# SCH_10edm_2026-03-11.net
KiCad netlist of a schematic drawn in EasyEDA
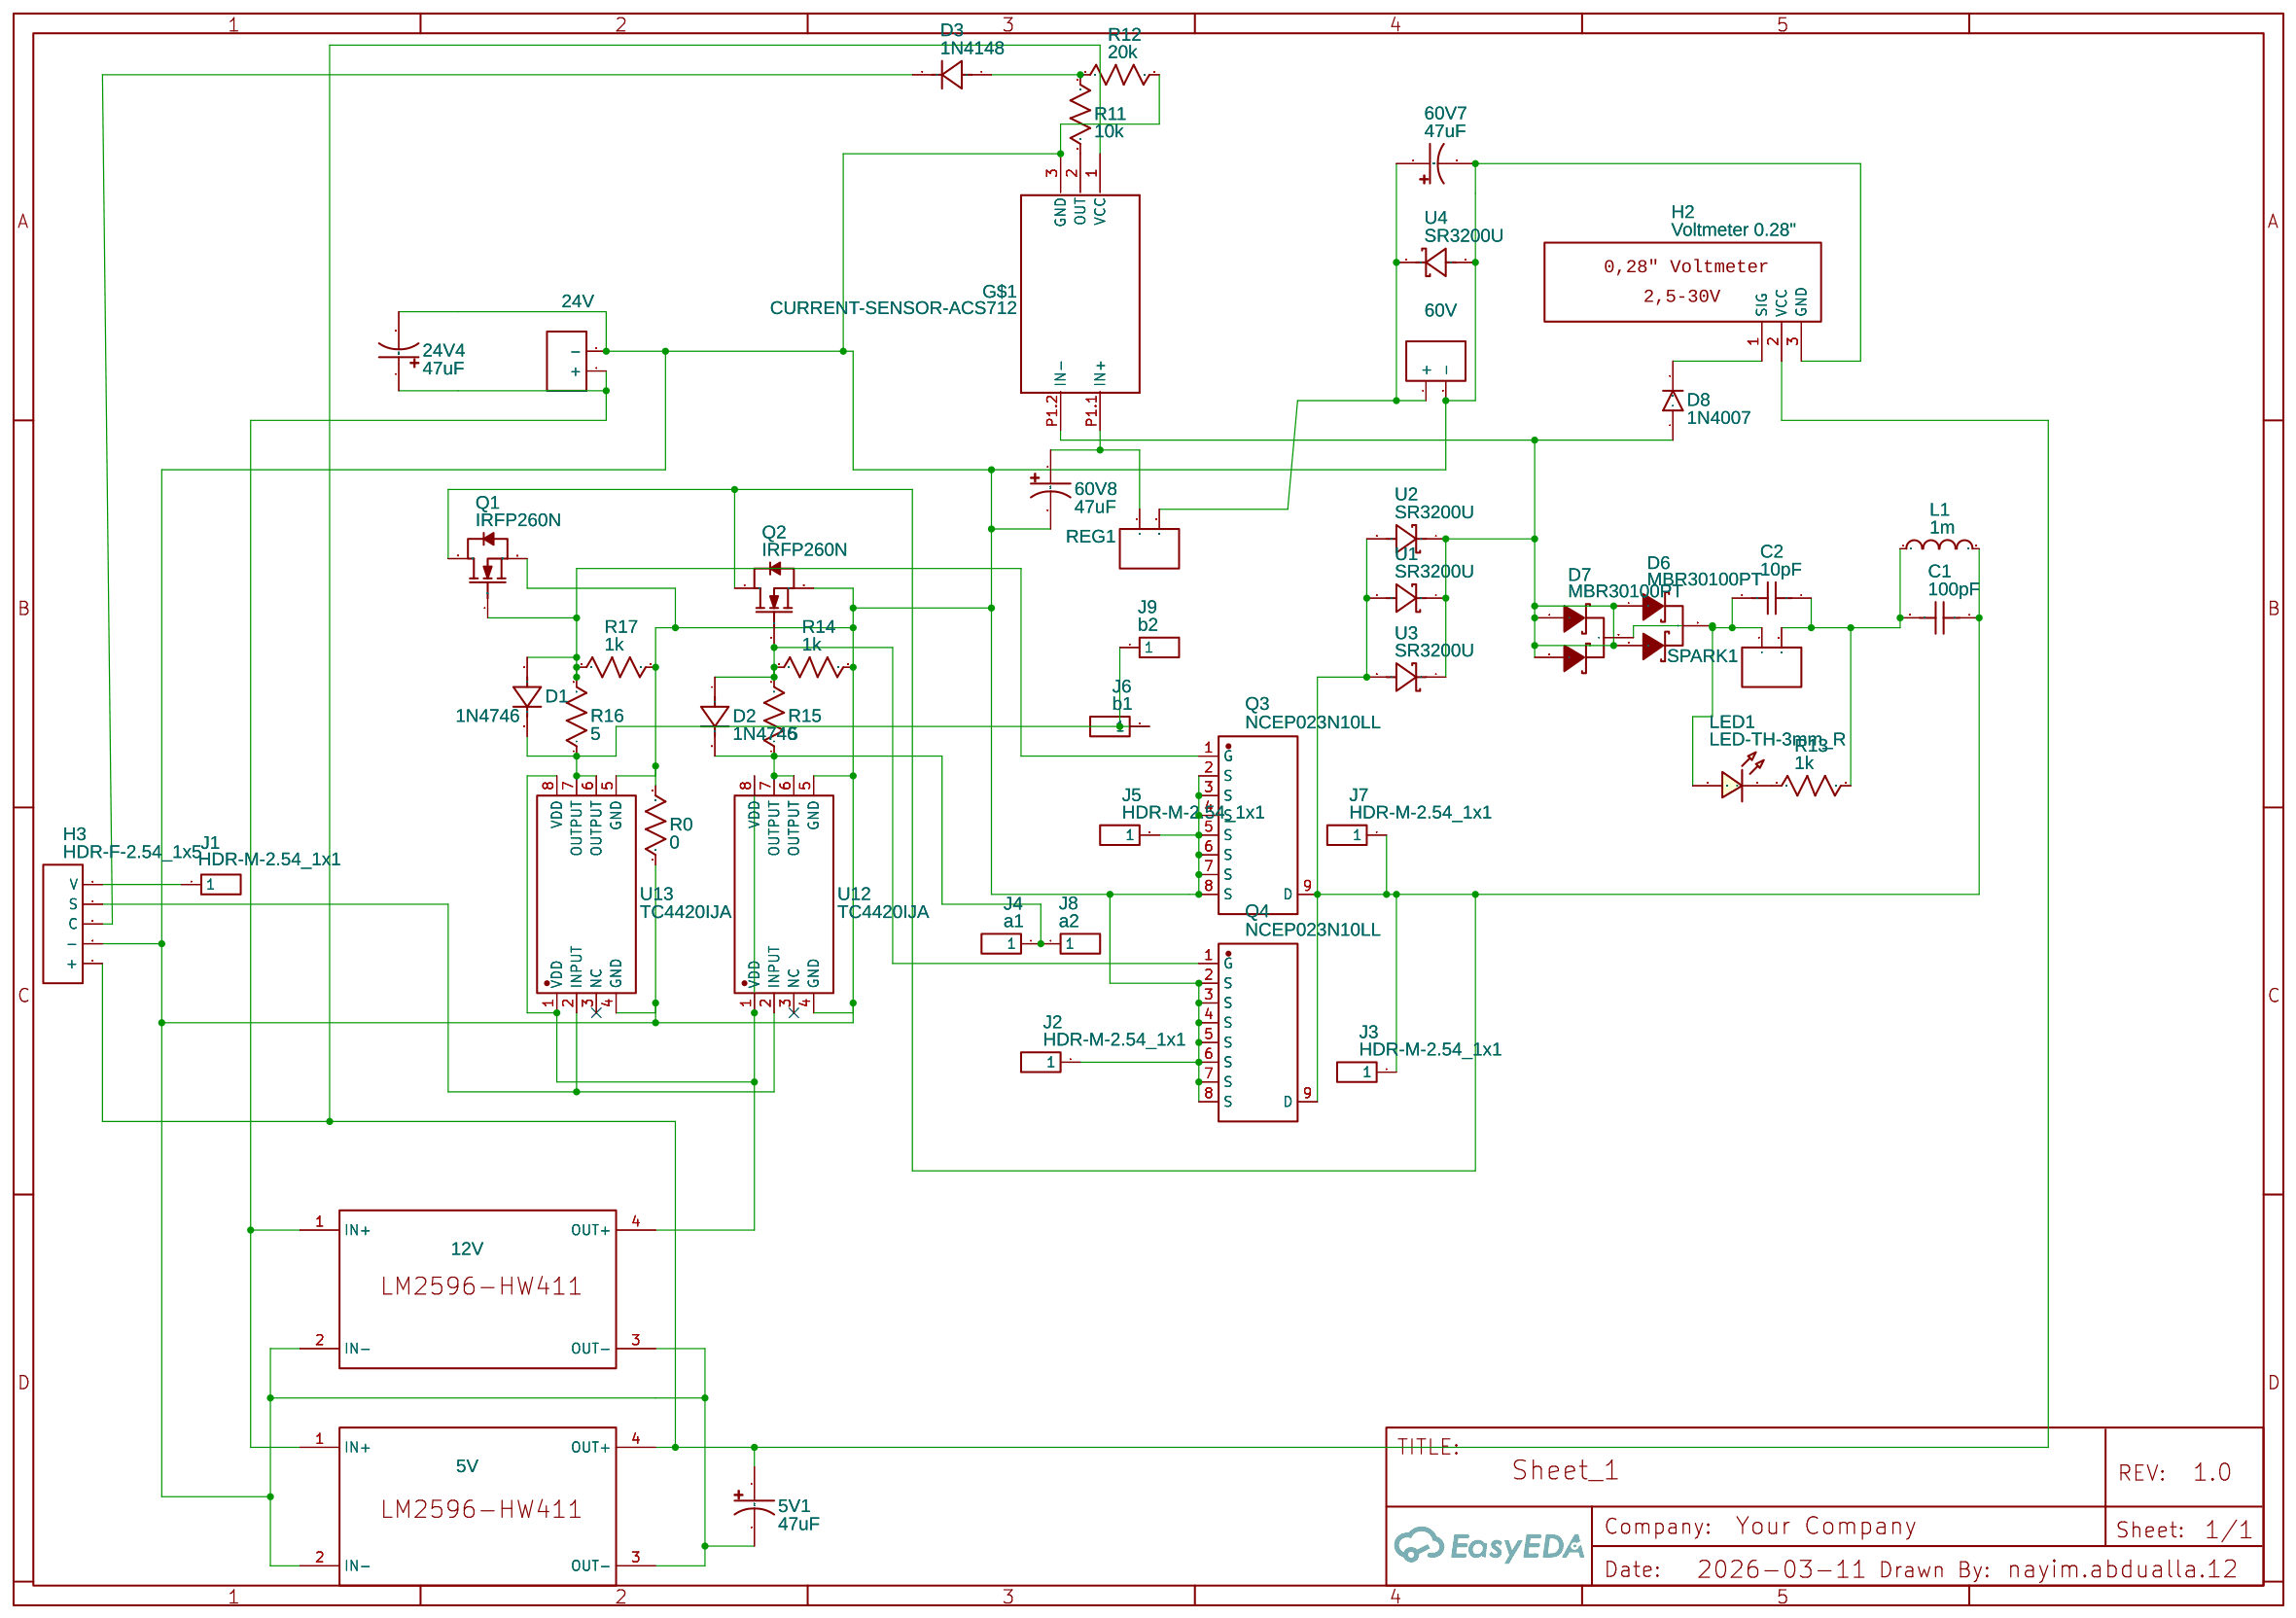
[diagram p0: schematic sheet]

(export (version "E")
  (design (tool "Eeschema 10.0.6"))
  (components
    (comp (ref "5V") (value "LM2596-HW411") (libsource (lib "") (part "LM2596-HW411")))
    (comp (ref "5V1")
      (value "47uF")
      (fields
        (field (name "Manufacturer Part") "NFK160V47M10*16 3.5CC")
        (field (name "Manufacturer") "SAMYOUNG(韩国三莹)")
      )
      (libsource (lib "") (part "NFK160VB47M10*16_3.5CC_3"))
    )
    (comp (ref "12V") (value "LM2596-HW411") (libsource (lib "") (part "LM2596-HW411_1")))
    (comp (ref "24V") (value "CONN-TH_2P-P5.00") (libsource (lib "") (part "CONN-TH_2P-P5.00_2")))
    (comp (ref "24V4")
      (value "47uF")
      (fields
        (field (name "Manufacturer Part") "NFK160V47M10*16 3.5CC")
        (field (name "Manufacturer") "SAMYOUNG(韩国三莹)")
      )
      (libsource (lib "") (part "NFK160VB47M10*16_3.5CC_1"))
    )
    (comp (ref "60V") (value "CONN-TH_2P-P5.00") (libsource (lib "") (part "CONN-TH_2P-P5.00_3")))
    (comp (ref "60V7")
      (value "47uF")
      (fields
        (field (name "Manufacturer Part") "NFK160V47M10*16 3.5CC")
        (field (name "Manufacturer") "SAMYOUNG(韩国三莹)")
      )
      (libsource (lib "") (part "NFK160VB47M10*16_3.5CC"))
    )
    (comp (ref "60V8")
      (value "47uF")
      (fields
        (field (name "Manufacturer Part") "NFK160V47M10*16 3.5CC")
        (field (name "Manufacturer") "SAMYOUNG(韩国三莹)")
      )
      (libsource (lib "") (part "NFK160VB47M10*16_3.5CC_2"))
    )
    (comp (ref "C1")
      (value "100pF")
      (fields (field (name "Manufacturer Part") "R06B1B101KQ0T0S0N0") (field (name "Manufacturer") "STE(松田)"))
      (libsource (lib "") (part "R06B1B101KQ0T0S0N0"))
    )
    (comp (ref "C2")
      (value "10pF")
      (fields (field (name "Manufacturer Part") "R06B1B101KQ0T0S0N0") (field (name "Manufacturer") "STE(松田)"))
      (libsource (lib "") (part "R06B1B101KQ0T0S0N0"))
    )
    (comp (ref "D1")
      (value "1N4746")
      (fields (field (name "Manufacturer Part") "1N4148") (field (name "Manufacturer") "LJ(朗捷)"))
      (libsource (lib "") (part "1N4148_C18195411"))
    )
    (comp (ref "D2")
      (value "1N4746")
      (fields (field (name "Manufacturer Part") "1N4148") (field (name "Manufacturer") "LJ(朗捷)"))
      (libsource (lib "") (part "1N4148_C18195411"))
    )
    (comp (ref "D3")
      (value "1N4148")
      (fields (field (name "Manufacturer") "LJ(朗捷)"))
      (libsource (lib "") (part "1N4148_C18195411_1"))
    )
    (comp (ref "D6")
      (value "MBR30100PT")
      (fields (field (name "Manufacturer") "PANJIT"))
      (libsource (lib "") (part "MBR30100PT"))
    )
    (comp (ref "D7")
      (value "MBR30100PT")
      (fields (field (name "Manufacturer") "PANJIT"))
      (libsource (lib "") (part "MBR30100PT"))
    )
    (comp (ref "D8")
      (value "1N4007")
      (fields (field (name "Manufacturer") "STARSEA"))
      (libsource (lib "") (part "1N4007"))
    )
    (comp (ref "G$1") (value "CURRENT-SENSOR-ACS712") (libsource (lib "") (part "CURRENT-SENSOR-ACS712")))
    (comp (ref "H2") (value "Voltmeter 0.28\"") (libsource (lib "") (part "Voltmeter 0.28{dblquote}")))
    (comp (ref "H3") (value "HDR-F-2.54_1x5") (libsource (lib "") (part "HDR-F-2.54_1x5")))
    (comp (ref "J1") (value "HDR-M-2.54_1x1") (libsource (lib "") (part "HDR-M-2.54_1x1_1")))
    (comp (ref "J2") (value "HDR-M-2.54_1x1") (libsource (lib "") (part "HDR-M-2.54_1x1")))
    (comp (ref "J3") (value "HDR-M-2.54_1x1") (libsource (lib "") (part "HDR-M-2.54_1x1")))
    (comp (ref "J4") (value "a1") (libsource (lib "") (part "HDR-M-2.54_1x1")))
    (comp (ref "J5") (value "HDR-M-2.54_1x1") (libsource (lib "") (part "HDR-M-2.54_1x1")))
    (comp (ref "J6") (value "b1") (libsource (lib "") (part "HDR-M-2.54_1x1")))
    (comp (ref "J7") (value "HDR-M-2.54_1x1") (libsource (lib "") (part "HDR-M-2.54_1x1")))
    (comp (ref "J8") (value "a2") (libsource (lib "") (part "HDR-M-2.54_1x1_1")))
    (comp (ref "J9") (value "b2") (libsource (lib "") (part "HDR-M-2.54_1x1_1")))
    (comp (ref "L1") (value "1m") (libsource (lib "") (part "L_AXIAL-0.6_US")))
    (comp (ref "LED1")
      (value "LED-TH-3mm_R")
      (fields
        (field (name "Manufacturer Part") "204-10SDRD/S530-A3-L")
        (field (name "Manufacturer") "EVERLIGHT(台湾亿光)")
      )
      (libsource (lib "") (part "LED-TH-3mm_R"))
    )
    (comp (ref "Q1")
      (value "IRFP260N")
      (fields (field (name "Manufacturer") "minos(迈诺斯)"))
      (libsource (lib "") (part "IRFP260N"))
    )
    (comp (ref "Q2")
      (value "IRFP260N")
      (fields (field (name "Manufacturer") "minos(迈诺斯)"))
      (libsource (lib "") (part "IRFP260N"))
    )
    (comp (ref "Q3")
      (value "NCEP023N10LL")
      (fields (field (name "Manufacturer") "NCE(无锡新洁能)"))
      (libsource (lib "") (part "NCEP023N10LL"))
    )
    (comp (ref "Q4")
      (value "NCEP023N10LL")
      (fields (field (name "Manufacturer") "NCE(无锡新洁能)"))
      (libsource (lib "") (part "NCEP023N10LL"))
    )
    (comp (ref "R0") (value "0") (libsource (lib "") (part "R_AXIAL-0.4_US_1")))
    (comp (ref "R11") (value "10k") (libsource (lib "") (part "R_AXIAL-0.4_US_1")))
    (comp (ref "R12") (value "20k") (libsource (lib "") (part "R_AXIAL-0.4_US")))
    (comp (ref "R13") (value "1k") (libsource (lib "") (part "R_AXIAL-0.4_US_2")))
    (comp (ref "R14") (value "1k") (libsource (lib "") (part "R_AXIAL-0.4_US")))
    (comp (ref "R15") (value "5") (libsource (lib "") (part "R_AXIAL-0.4_US_1")))
    (comp (ref "R16") (value "5") (libsource (lib "") (part "R_AXIAL-0.4_US_1")))
    (comp (ref "R17") (value "1k") (libsource (lib "") (part "R_AXIAL-0.4_US")))
    (comp (ref "REG1") (value "CONN-TH_2P-P5.00") (libsource (lib "") (part "CONN-TH_2P-P5.00_1")))
    (comp (ref "SPARK1") (value "CONN-TH_2P-P5.00") (libsource (lib "") (part "CONN-TH_2P-P5.00")))
    (comp (ref "U1")
      (value "SR3200U")
      (fields (field (name "Manufacturer") "DIYI(迪一/芯诺)"))
      (libsource (lib "") (part "SR3200U"))
    )
    (comp (ref "U2")
      (value "SR3200U")
      (fields (field (name "Manufacturer") "DIYI(迪一/芯诺)"))
      (libsource (lib "") (part "SR3200U"))
    )
    (comp (ref "U3")
      (value "SR3200U")
      (fields (field (name "Manufacturer") "DIYI(迪一/芯诺)"))
      (libsource (lib "") (part "SR3200U"))
    )
    (comp (ref "U4")
      (value "SR3200U")
      (fields (field (name "Manufacturer") "DIYI(迪一/芯诺)"))
      (libsource (lib "") (part "SR3200U_1"))
    )
    (comp (ref "U12")
      (value "TC4420IJA")
      (fields (field (name "Manufacturer") "MICROCHIP(美国微芯)"))
      (libsource (lib "") (part "TC4420IJA"))
    )
    (comp (ref "U13")
      (value "TC4420IJA")
      (fields (field (name "Manufacturer") "MICROCHIP(美国微芯)"))
      (libsource (lib "") (part "TC4420IJA"))
    )
  )
  (nets
    (net (code "1") (name "Net-(5V-OUT+)") (class "Default")
      (node (ref "5V") (pin "4") (pinfunction "OUT+_4") (pintype "unspecified"))
      (node (ref "5V1") (pin "1") (pinfunction "1_1") (pintype "unspecified"))
      (node (ref "G$1") (pin "1") (pinfunction "VCC_1") (pintype "bidirectional"))
      (node (ref "H2") (pin "2") (pinfunction "VCC_2") (pintype "unspecified"))
      (node (ref "H3") (pin "1") (pinfunction "+_1") (pintype "unspecified"))
    )
    (net (code "2") (name "Net-(12V-IN+)") (class "Default")
      (node (ref "12V") (pin "1") (pinfunction "IN+_1") (pintype "unspecified"))
      (node (ref "24V") (pin "1") (pinfunction "+_1") (pintype "unspecified"))
      (node (ref "24V4") (pin "1") (pinfunction "1_1") (pintype "unspecified"))
      (node (ref "5V") (pin "1") (pinfunction "IN+_1") (pintype "unspecified"))
    )
    (net (code "3") (name "Net-(12V-IN-)") (class "Default")
      (node (ref "12V") (pin "2") (pinfunction "IN-_2") (pintype "unspecified"))
      (node (ref "12V") (pin "3") (pinfunction "OUT-_3") (pintype "unspecified"))
      (node (ref "24V") (pin "2") (pinfunction "-_2") (pintype "unspecified"))
      (node (ref "24V4") (pin "2") (pinfunction "2_2") (pintype "unspecified"))
      (node (ref "5V") (pin "2") (pinfunction "IN-_2") (pintype "unspecified"))
      (node (ref "5V") (pin "3") (pinfunction "OUT-_3") (pintype "unspecified"))
      (node (ref "5V1") (pin "2") (pinfunction "2_2") (pintype "unspecified"))
      (node (ref "60V") (pin "2") (pinfunction "-_2") (pintype "unspecified"))
      (node (ref "60V7") (pin "2") (pinfunction "2_2") (pintype "unspecified"))
      (node (ref "60V8") (pin "2") (pinfunction "2_2") (pintype "unspecified"))
      (node (ref "G$1") (pin "3") (pinfunction "GND_3") (pintype "bidirectional"))
      (node (ref "H2") (pin "3") (pinfunction "GND_3") (pintype "unspecified"))
      (node (ref "H3") (pin "2") (pinfunction "-_2") (pintype "unspecified"))
      (node (ref "J2") (pin "1") (pinfunction "1_1") (pintype "input"))
      (node (ref "J5") (pin "1") (pinfunction "1_1") (pintype "input"))
      (node (ref "Q1") (pin "3") (pinfunction "S_3") (pintype "unspecified"))
      (node (ref "Q2") (pin "3") (pinfunction "S_3") (pintype "unspecified"))
      (node (ref "Q3") (pin "2") (pinfunction "S_2") (pintype "unspecified"))
      (node (ref "Q3") (pin "3") (pinfunction "S_3") (pintype "unspecified"))
      (node (ref "Q3") (pin "4") (pinfunction "S_4") (pintype "unspecified"))
      (node (ref "Q3") (pin "5") (pinfunction "S_5") (pintype "unspecified"))
      (node (ref "Q3") (pin "6") (pinfunction "S_6") (pintype "unspecified"))
      (node (ref "Q3") (pin "7") (pinfunction "S_7") (pintype "unspecified"))
      (node (ref "Q3") (pin "8") (pinfunction "S_8") (pintype "unspecified"))
      (node (ref "Q4") (pin "2") (pinfunction "S_2") (pintype "unspecified"))
      (node (ref "Q4") (pin "3") (pinfunction "S_3") (pintype "unspecified"))
      (node (ref "Q4") (pin "4") (pinfunction "S_4") (pintype "unspecified"))
      (node (ref "Q4") (pin "5") (pinfunction "S_5") (pintype "unspecified"))
      (node (ref "Q4") (pin "6") (pinfunction "S_6") (pintype "unspecified"))
      (node (ref "Q4") (pin "7") (pinfunction "S_7") (pintype "unspecified"))
      (node (ref "Q4") (pin "8") (pinfunction "S_8") (pintype "unspecified"))
      (node (ref "R0") (pin "1") (pinfunction "1_1") (pintype "unspecified"))
      (node (ref "R0") (pin "2") (pinfunction "2_2") (pintype "unspecified"))
      (node (ref "R12") (pin "2") (pinfunction "2_2") (pintype "unspecified"))
      (node (ref "R14") (pin "2") (pinfunction "2_2") (pintype "unspecified"))
      (node (ref "R17") (pin "2") (pinfunction "2_2") (pintype "unspecified"))
      (node (ref "U12") (pin "4") (pinfunction "GND_4") (pintype "unspecified"))
      (node (ref "U12") (pin "5") (pinfunction "GND_5") (pintype "unspecified"))
      (node (ref "U13") (pin "4") (pinfunction "GND_4") (pintype "unspecified"))
      (node (ref "U13") (pin "5") (pinfunction "GND_5") (pintype "unspecified"))
      (node (ref "U4") (pin "2") (pinfunction "A_2") (pintype "unspecified"))
    )
    (net (code "4") (name "Net-(12V-OUT+)") (class "Default")
      (node (ref "12V") (pin "4") (pinfunction "OUT+_4") (pintype "unspecified"))
      (node (ref "U12") (pin "1") (pinfunction "VDD_1") (pintype "unspecified"))
      (node (ref "U12") (pin "8") (pinfunction "VDD_8") (pintype "unspecified"))
      (node (ref "U13") (pin "1") (pinfunction "VDD_1") (pintype "unspecified"))
      (node (ref "U13") (pin "8") (pinfunction "VDD_8") (pintype "unspecified"))
    )
    (net (code "5") (name "Net-(60V-+)") (class "Default")
      (node (ref "60V") (pin "1") (pinfunction "+_1") (pintype "unspecified"))
      (node (ref "60V7") (pin "1") (pinfunction "1_1") (pintype "unspecified"))
      (node (ref "REG1") (pin "2") (pinfunction "2_2") (pintype "unspecified"))
      (node (ref "U4") (pin "1") (pinfunction "1_1") (pintype "unspecified"))
    )
    (net (code "6") (name "Net-(C1-Pad2)") (class "Default")
      (node (ref "C1") (pin "2") (pinfunction "2_2") (pintype "unspecified"))
      (node (ref "C2") (pin "1") (pinfunction "1_1") (pintype "unspecified"))
      (node (ref "L1") (pin "1") (pinfunction "1_1") (pintype "unspecified"))
      (node (ref "R13") (pin "1") (pinfunction "1_1") (pintype "unspecified"))
      (node (ref "SPARK1") (pin "2") (pinfunction "2_2") (pintype "unspecified"))
    )
    (net (code "7") (name "Net-(D1-A)") (class "Default")
      (node (ref "D1") (pin "1") (pinfunction "A_1") (pintype "unspecified"))
      (node (ref "Q1") (pin "1") (pinfunction "G_1") (pintype "unspecified"))
      (node (ref "Q3") (pin "1") (pinfunction "G_1") (pintype "unspecified"))
      (node (ref "R16") (pin "2") (pinfunction "2_2") (pintype "unspecified"))
      (node (ref "R17") (pin "1") (pinfunction "1_1") (pintype "unspecified"))
    )
    (net (code "8") (name "Net-(D1-C)") (class "Default")
      (node (ref "D1") (pin "2") (pinfunction "C_2") (pintype "unspecified"))
      (node (ref "J6") (pin "1") (pinfunction "1_1") (pintype "input"))
      (node (ref "J9") (pin "1") (pinfunction "1_1") (pintype "input"))
      (node (ref "R16") (pin "1") (pinfunction "1_1") (pintype "unspecified"))
      (node (ref "U13") (pin "6") (pinfunction "OUTPUT_6") (pintype "unspecified"))
      (node (ref "U13") (pin "7") (pinfunction "OUTPUT_7") (pintype "unspecified"))
    )
    (net (code "9") (name "Net-(D2-A)") (class "Default")
      (node (ref "D2") (pin "1") (pinfunction "A_1") (pintype "unspecified"))
      (node (ref "Q2") (pin "1") (pinfunction "G_1") (pintype "unspecified"))
      (node (ref "Q4") (pin "1") (pinfunction "G_1") (pintype "unspecified"))
      (node (ref "R14") (pin "1") (pinfunction "1_1") (pintype "unspecified"))
      (node (ref "R15") (pin "2") (pinfunction "2_2") (pintype "unspecified"))
    )
    (net (code "10") (name "Net-(D2-C)") (class "Default")
      (node (ref "D2") (pin "2") (pinfunction "C_2") (pintype "unspecified"))
      (node (ref "J4") (pin "1") (pinfunction "1_1") (pintype "input"))
      (node (ref "J8") (pin "1") (pinfunction "1_1") (pintype "input"))
      (node (ref "R15") (pin "1") (pinfunction "1_1") (pintype "unspecified"))
      (node (ref "U12") (pin "6") (pinfunction "OUTPUT_6") (pintype "unspecified"))
      (node (ref "U12") (pin "7") (pinfunction "OUTPUT_7") (pintype "unspecified"))
    )
    (net (code "11") (name "Net-(D3-A)") (class "Default")
      (node (ref "D3") (pin "1") (pinfunction "A_1") (pintype "unspecified"))
      (node (ref "R11") (pin "2") (pinfunction "2_2") (pintype "unspecified"))
      (node (ref "R12") (pin "1") (pinfunction "1_1") (pintype "unspecified"))
    )
    (net (code "12") (name "Net-(D3-C)") (class "Default")
      (node (ref "D3") (pin "2") (pinfunction "C_2") (pintype "unspecified"))
      (node (ref "H3") (pin "3") (pinfunction "C_3") (pintype "unspecified"))
    )
    (net (code "13") (name "Net-(D6-K)") (class "Default")
      (node (ref "C2") (pin "2") (pinfunction "2_2") (pintype "unspecified"))
      (node (ref "D6") (pin "2") (pinfunction "K_2") (pintype "unspecified"))
      (node (ref "D7") (pin "2") (pinfunction "K_2") (pintype "unspecified"))
      (node (ref "LED1") (pin "1") (pinfunction "1_1") (pintype "unspecified"))
      (node (ref "SPARK1") (pin "1") (pinfunction "1_1") (pintype "unspecified"))
    )
    (net (code "14") (name "Net-(D8-A)") (class "Default")
      (node (ref "D6") (pin "1") (pinfunction "A_1") (pintype "unspecified"))
      (node (ref "D6") (pin "3") (pinfunction "A_3") (pintype "unspecified"))
      (node (ref "D7") (pin "1") (pinfunction "A_1") (pintype "unspecified"))
      (node (ref "D7") (pin "3") (pinfunction "A_3") (pintype "unspecified"))
      (node (ref "D8") (pin "1") (pinfunction "A_1") (pintype "unspecified"))
      (node (ref "G$1") (pin "P1.2") (pinfunction "IN-_P1.2") (pintype "bidirectional"))
      (node (ref "U1") (pin "1") (pinfunction "1_1") (pintype "unspecified"))
      (node (ref "U2") (pin "1") (pinfunction "1_1") (pintype "unspecified"))
      (node (ref "U3") (pin "1") (pinfunction "1_1") (pintype "unspecified"))
    )
    (net (code "15") (name "Net-(D8-C)") (class "Default")
      (node (ref "D8") (pin "2") (pinfunction "C_2") (pintype "unspecified"))
      (node (ref "H2") (pin "1") (pinfunction "SIG_1") (pintype "unspecified"))
    )
    (net (code "16") (name "Net-(G$1-IN+)") (class "Default")
      (node (ref "60V8") (pin "1") (pinfunction "1_1") (pintype "unspecified"))
      (node (ref "G$1") (pin "P1.1") (pinfunction "IN+_P1.1") (pintype "bidirectional"))
      (node (ref "REG1") (pin "1") (pinfunction "1_1") (pintype "unspecified"))
    )
    (net (code "17") (name "Net-(G$1-OUT)") (class "Default")
      (node (ref "G$1") (pin "2") (pinfunction "OUT_2") (pintype "bidirectional"))
      (node (ref "R11") (pin "1") (pinfunction "1_1") (pintype "unspecified"))
    )
    (net (code "18") (name "Net-(H3-S)") (class "Default")
      (node (ref "H3") (pin "4") (pinfunction "S_4") (pintype "unspecified"))
      (node (ref "U12") (pin "2") (pinfunction "INPUT_2") (pintype "unspecified"))
      (node (ref "U13") (pin "2") (pinfunction "INPUT_2") (pintype "unspecified"))
    )
    (net (code "19") (name "Net-(H3-V)") (class "Default")
      (node (ref "H3") (pin "5") (pinfunction "V_5") (pintype "unspecified"))
      (node (ref "J1") (pin "1") (pinfunction "1_1") (pintype "input"))
    )
    (net (code "20") (name "Net-(LED1-Pad2)") (class "Default")
      (node (ref "LED1") (pin "2") (pinfunction "2_2") (pintype "unspecified"))
      (node (ref "R13") (pin "2") (pinfunction "2_2") (pintype "unspecified"))
    )
    (net (code "21") (name "Net-(Q1-D)") (class "Default")
      (node (ref "C1") (pin "1") (pinfunction "1_1") (pintype "unspecified"))
      (node (ref "J3") (pin "1") (pinfunction "1_1") (pintype "input"))
      (node (ref "J7") (pin "1") (pinfunction "1_1") (pintype "input"))
      (node (ref "L1") (pin "2") (pinfunction "2_2") (pintype "unspecified"))
      (node (ref "Q1") (pin "2") (pinfunction "D_2") (pintype "unspecified"))
      (node (ref "Q2") (pin "2") (pinfunction "D_2") (pintype "unspecified"))
      (node (ref "Q3") (pin "9") (pinfunction "D_9") (pintype "unspecified"))
      (node (ref "Q4") (pin "9") (pinfunction "D_9") (pintype "unspecified"))
      (node (ref "U1") (pin "2") (pinfunction "A_2") (pintype "unspecified"))
      (node (ref "U2") (pin "2") (pinfunction "A_2") (pintype "unspecified"))
      (node (ref "U3") (pin "2") (pinfunction "A_2") (pintype "unspecified"))
    )
    (net (code "22") (name "unconnected-(U12-NC-Pad3)") (class "Default")
      (node (ref "U12") (pin "3") (pinfunction "NC_3") (pintype "unspecified+no_connect"))
    )
    (net (code "23") (name "unconnected-(U13-NC-Pad3)") (class "Default")
      (node (ref "U13") (pin "3") (pinfunction "NC_3") (pintype "unspecified+no_connect"))
    )
  )
)
